# Pmaster-A9112-remote_1.net
KiCad netlist of a schematic drawn in Altium Designer
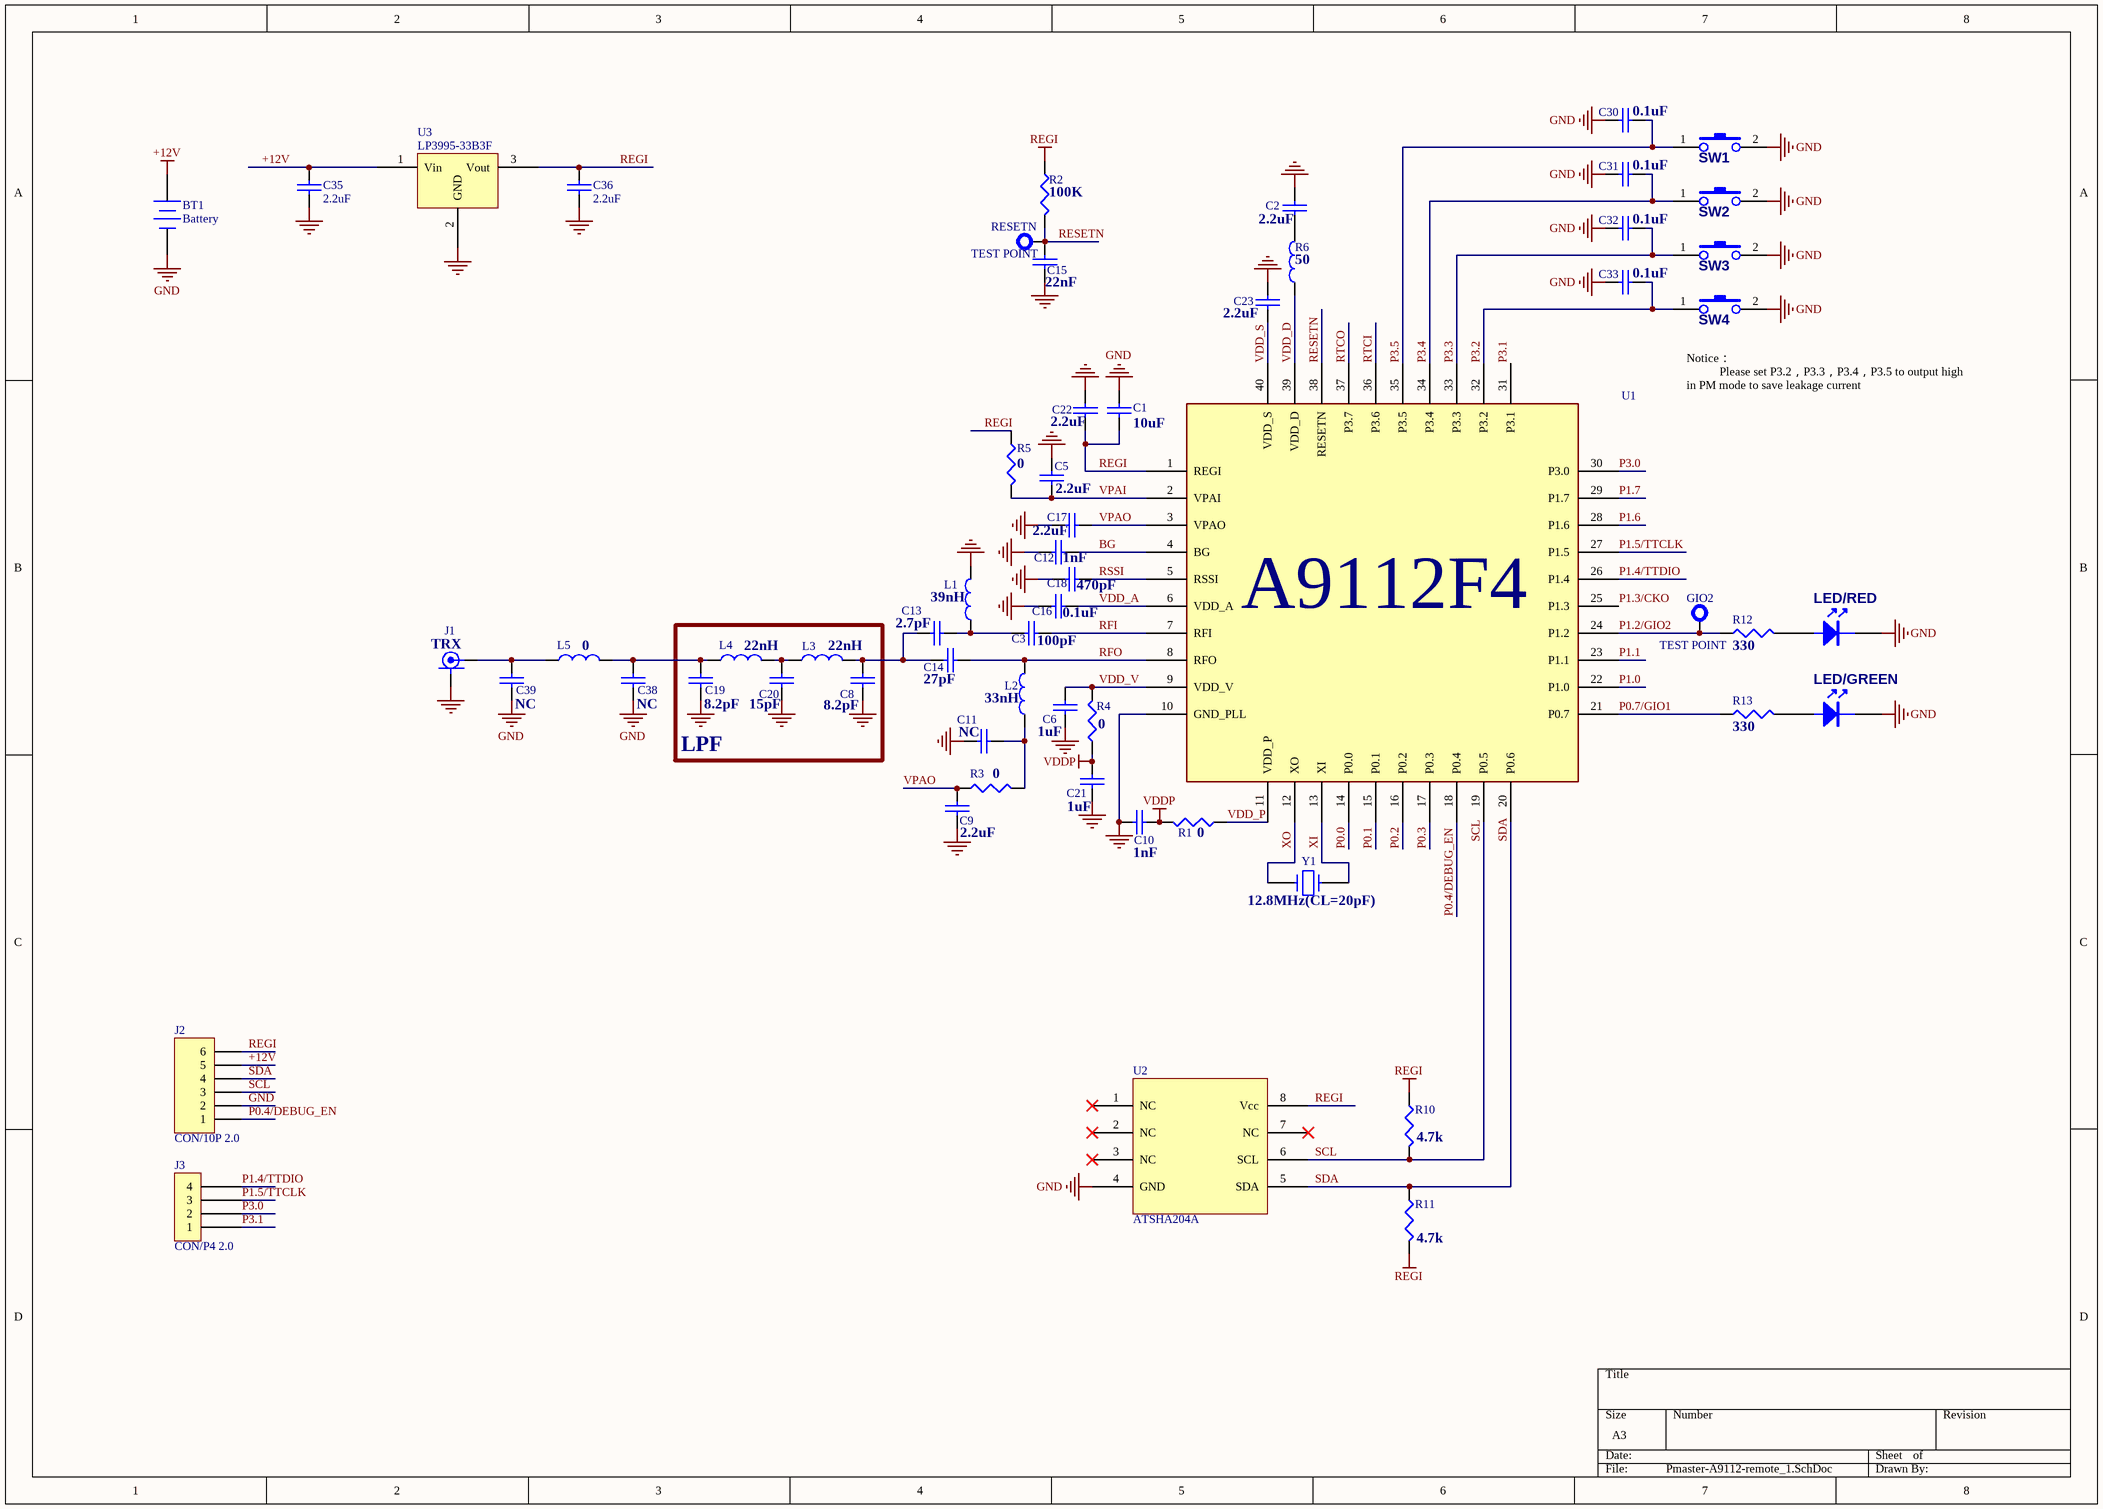
[diagram p0: Pmaster-A9112-remote_1.SchDoc]

(export (version "E")
  (design (tool "Eeschema 10.0.6"))
  (components
    (comp (ref "BT1")
      (value "Battery")
      (footprint "BAT-2")
      (description "Multicell Battery")
      (fields (field (name "PUBLISHER") "Altium Limited"))
      (libsource (lib "Miscellaneous Devices") (part "Battery"))
    )
    (comp (ref "C1") (value "10uF") (footprint "1206") (libsource (lib "*") (part "CAP")))
    (comp (ref "C2") (value "2.2uF") (footprint "0603") (libsource (lib "*") (part "CAP")))
    (comp (ref "C3") (value "100pF") (footprint "0402") (libsource (lib "*") (part "CAP")))
    (comp (ref "C5") (value "2.2uF") (footprint "0603") (libsource (lib "*") (part "CAP")))
    (comp (ref "C6") (value "1uF") (footprint "0603") (libsource (lib "*") (part "CAP")))
    (comp (ref "C8") (value "8.2pF") (footprint "0402") (libsource (lib "*") (part "CAP")))
    (comp (ref "C9")
      (value "2.2uF")
      (footprint "0603")
      (description "Chip C")
      (libsource (lib "*") (part "C/0603"))
    )
    (comp (ref "C10") (value "1nF") (footprint "0402") (libsource (lib "*") (part "CAP")))
    (comp (ref "C11")
      (value "NC")
      (footprint "0402")
      (description "Chip C")
      (libsource (lib "*") (part "C/0603"))
    )
    (comp (ref "C12") (value "1nF") (footprint "0402") (libsource (lib "*") (part "CAP")))
    (comp (ref "C13") (value "2.7pF") (footprint "0402") (libsource (lib "*") (part "CAP")))
    (comp (ref "C14") (value "27pF") (footprint "0402") (libsource (lib "*") (part "CAP")))
    (comp (ref "C15")
      (value "22nF")
      (footprint "0402")
      (description "Chip C")
      (libsource (lib "*") (part "C/1206"))
    )
    (comp (ref "C16") (value "0.1uF") (footprint "0603") (libsource (lib "*") (part "CAP")))
    (comp (ref "C17")
      (value "2.2uF")
      (footprint "0603")
      (description "Chip C")
      (libsource (lib "*") (part "C/0603"))
    )
    (comp (ref "C18") (value "470pF") (footprint "0402") (libsource (lib "*") (part "CAP")))
    (comp (ref "C19")
      (value "8.2pF")
      (footprint "0402")
      (description "Chip C")
      (libsource (lib "*") (part "C/0603"))
    )
    (comp (ref "C20")
      (value "15pF")
      (footprint "0402")
      (description "Chip C")
      (libsource (lib "*") (part "C/0603"))
    )
    (comp (ref "C21") (value "1uF") (footprint "0402") (libsource (lib "*") (part "CAP")))
    (comp (ref "C22") (value "2.2uF") (footprint "0603") (libsource (lib "*") (part "CAP")))
    (comp (ref "C23") (value "2.2uF") (footprint "0603") (libsource (lib "*") (part "CAP")))
    (comp (ref "C30") (value "0.1uF") (footprint "0603") (libsource (lib "*") (part "CAP")))
    (comp (ref "C31") (value "0.1uF") (footprint "0603") (libsource (lib "*") (part "CAP")))
    (comp (ref "C32") (value "0.1uF") (footprint "0603") (libsource (lib "*") (part "CAP")))
    (comp (ref "C33") (value "0.1uF") (footprint "0603") (libsource (lib "*") (part "CAP")))
    (comp (ref "C35") (value "2.2uF") (footprint "0603") (libsource (lib "") (part "CAP_1")))
    (comp (ref "C36")
      (value "2.2uF")
      (footprint "0603")
      (description "Chip C")
      (libsource (lib "*") (part "C/0603"))
    )
    (comp (ref "C38")
      (value "NC")
      (footprint "0402")
      (description "Chip C")
      (libsource (lib "*") (part "C/0603"))
    )
    (comp (ref "C39")
      (value "NC")
      (footprint "0402")
      (description "Chip C")
      (libsource (lib "*") (part "C/0603"))
    )
    (comp (ref "GIO2") (value "TEST POINT") (footprint "DIPOLE") (libsource (lib "my-amiccom") (part "TP")))
    (comp (ref "J1") (value "TRX") (footprint "SMA CONNECTOR") (libsource (lib "*") (part "SMA CONNECTOR")))
    (comp (ref "J2")
      (value "CON/10P 2.0")
      (footprint "HDR10_2.0")
      (description "Hole 36mil")
      (libsource (lib "my-amiccom") (part "CON/6P 2.0"))
    )
    (comp (ref "J3") (value "CON/P4 2.0") (libsource (lib "my-amiccom") (part "CON/P4 2.54")))
    (comp (ref "L1")
      (value "39nH")
      (footprint "0402")
      (description "Chip L")
      (libsource (lib "*") (part "L/0402"))
    )
    (comp (ref "L2")
      (value "33nH")
      (footprint "0402")
      (description "Chip L")
      (libsource (lib "*") (part "L/0402"))
    )
    (comp (ref "L3") (value "22nH") (footprint "0402") (libsource (lib "*") (part "L/0603")))
    (comp (ref "L4") (value "22nH") (footprint "0402") (libsource (lib "*") (part "L/0603")))
    (comp (ref "L5") (value "0") (footprint "0402") (libsource (lib "*") (part "L/0603")))
    (comp (ref "LED/GREEN")
      (value "LED/GREEN")
      (footprint "0603")
      (libsource (lib "my-amiccom") (part "LED"))
    )
    (comp (ref "LED/RED") (value "LED/RED") (footprint "0603") (libsource (lib "my-amiccom") (part "LED")))
    (comp (ref "R1") (value "0") (footprint "0402") (libsource (lib "*") (part "RES1")))
    (comp (ref "R2")
      (value "100K")
      (footprint "0402")
      (description "Chip R")
      (libsource (lib "*") (part "R/0402"))
    )
    (comp (ref "R3")
      (value "0")
      (footprint "0402")
      (description "Chip  R")
      (libsource (lib "*") (part "R/0603"))
    )
    (comp (ref "R4")
      (value "0")
      (footprint "0402")
      (description "Chip  R")
      (libsource (lib "*") (part "R/0603"))
    )
    (comp (ref "R5") (value "0") (footprint "0402") (libsource (lib "*") (part "RES1")))
    (comp (ref "R6") (value "50") (footprint "0402") (libsource (lib "") (part "L/0603_1")))
    (comp (ref "R10") (value "4.7k") (footprint "0402") (libsource (lib "*") (part "RES1")))
    (comp (ref "R11") (value "4.7k") (footprint "0402") (libsource (lib "*") (part "RES1")))
    (comp (ref "R12") (value "330") (footprint "0402") (libsource (lib "*") (part "RES1")))
    (comp (ref "R13") (value "330") (footprint "0402") (libsource (lib "*") (part "RES1")))
    (comp (ref "RESETN") (value "TEST POINT") (footprint "DIPOLE") (libsource (lib "my-amiccom") (part "TP")))
    (comp (ref "SW1")
      (value "SW-P~{B}2P")
      (footprint "SW2P")
      (libsource (lib "my-amiccom") (part "SW-PB{backslash}2P"))
    )
    (comp (ref "SW2")
      (value "SW-P~{B}2P")
      (footprint "SW2P")
      (libsource (lib "my-amiccom") (part "SW-PB{backslash}2P"))
    )
    (comp (ref "SW3")
      (value "SW-P~{B}2P")
      (footprint "SW2P")
      (libsource (lib "my-amiccom") (part "SW-PB{backslash}2P"))
    )
    (comp (ref "SW4")
      (value "SW-P~{B}2P")
      (footprint "SW2P")
      (libsource (lib "my-amiccom") (part "SW-PB{backslash}2P"))
    )
    (comp (ref "U1")
      (value "A9112F4")
      (footprint "QFN 5*5 40L")
      (libsource (lib "AMICCOM-S") (part "A9112F4"))
    )
    (comp (ref "U2") (value "ATSHA204A") (libsource (lib "my-amiccom") (part "ATSHA204A")))
    (comp (ref "U3")
      (value "LP3995-33B3F")
      (footprint "SOT-223")
      (description "GMT 3.3V REGULTOR")
      (libsource (lib "*") (part "REG{backslash}G903{backslash}3.3V{backslash}SOT-223"))
    )
    (comp (ref "Y1")
      (value "12.8MHz(CL=20pF)")
      (footprint "XTAL1")
      (description "Crystal")
      (libsource (lib "*") (part "CRYSTAL"))
    )
  )
  (nets
    (net (code "1") (name "+12V") (class "Default")
      (node (ref "BT1") (pin "1") (pinfunction "+_1") (pintype "passive"))
      (node (ref "C35") (pin "2") (pinfunction "2_2") (pintype "passive"))
      (node (ref "J2") (pin "5") (pinfunction "5_5") (pintype "passive"))
      (node (ref "U3") (pin "1") (pinfunction "Vin_1") (pintype "passive"))
    )
    (net (code "2") (name "/BG") (class "Default")
      (node (ref "C12") (pin "1") (pinfunction "1_1") (pintype "passive"))
      (node (ref "U1") (pin "4") (pinfunction "BG_4") (pintype "passive"))
    )
    (net (code "3") (name "/P0.0") (class "Default")
      (node (ref "U1") (pin "14") (pinfunction "P0.0_14") (pintype "passive"))
    )
    (net (code "4") (name "/P0.1") (class "Default")
      (node (ref "U1") (pin "15") (pinfunction "P0.1_15") (pintype "passive"))
    )
    (net (code "5") (name "/P0.2") (class "Default")
      (node (ref "U1") (pin "16") (pinfunction "P0.2_16") (pintype "passive"))
    )
    (net (code "6") (name "/P0.3") (class "Default")
      (node (ref "U1") (pin "17") (pinfunction "P0.3_17") (pintype "passive"))
    )
    (net (code "7") (name "/P0.4{slash}DEBUG_EN") (class "Default")
      (node (ref "J2") (pin "1") (pinfunction "1_1") (pintype "passive"))
      (node (ref "U1") (pin "18") (pinfunction "P0.4_18") (pintype "passive"))
    )
    (net (code "8") (name "/P0.7{slash}GIO1") (class "Default")
      (node (ref "R13") (pin "1") (pinfunction "1_1") (pintype "passive"))
      (node (ref "U1") (pin "21") (pinfunction "P0.7_21") (pintype "passive"))
    )
    (net (code "9") (name "/P1.0") (class "Default")
      (node (ref "U1") (pin "22") (pinfunction "P1.0_22") (pintype "passive"))
    )
    (net (code "10") (name "/P1.1") (class "Default")
      (node (ref "U1") (pin "23") (pinfunction "P1.1_23") (pintype "passive"))
    )
    (net (code "11") (name "/P1.2{slash}GIO2") (class "Default")
      (node (ref "GIO2") (pin "1") (pinfunction "1_1") (pintype "passive"))
      (node (ref "R12") (pin "1") (pinfunction "1_1") (pintype "passive"))
      (node (ref "U1") (pin "24") (pinfunction "P1.2_24") (pintype "passive"))
    )
    (net (code "12") (name "/P1.3{slash}CKO") (class "Default")
      (node (ref "U1") (pin "25") (pinfunction "P1.3_25") (pintype "passive"))
    )
    (net (code "13") (name "/P1.4{slash}TTDIO") (class "Default")
      (node (ref "J3") (pin "4") (pinfunction "4_4") (pintype "power_in"))
      (node (ref "U1") (pin "26") (pinfunction "P1.4_26") (pintype "passive"))
    )
    (net (code "14") (name "/P1.5{slash}TTCLK") (class "Default")
      (node (ref "J3") (pin "3") (pinfunction "3_3") (pintype "power_in"))
      (node (ref "U1") (pin "27") (pinfunction "P1.5_27") (pintype "passive"))
    )
    (net (code "15") (name "/P1.6") (class "Default")
      (node (ref "U1") (pin "28") (pinfunction "P1.6_28") (pintype "passive"))
    )
    (net (code "16") (name "/P1.7") (class "Default")
      (node (ref "U1") (pin "29") (pinfunction "P1.7_29") (pintype "passive"))
    )
    (net (code "17") (name "/P3.0") (class "Default")
      (node (ref "J3") (pin "2") (pinfunction "2_2") (pintype "power_in"))
      (node (ref "U1") (pin "30") (pinfunction "P3.0_30") (pintype "passive"))
    )
    (net (code "18") (name "/P3.1") (class "Default")
      (node (ref "J3") (pin "1") (pinfunction "1_1") (pintype "power_in"))
      (node (ref "U1") (pin "31") (pinfunction "P3.1_31") (pintype "passive"))
    )
    (net (code "19") (name "/P3.2") (class "Default")
      (node (ref "C33") (pin "2") (pinfunction "2_2") (pintype "passive"))
      (node (ref "SW4") (pin "1") (pinfunction "1_1") (pintype "passive"))
      (node (ref "U1") (pin "32") (pinfunction "P3.2_32") (pintype "passive"))
    )
    (net (code "20") (name "/P3.3") (class "Default")
      (node (ref "C32") (pin "2") (pinfunction "2_2") (pintype "passive"))
      (node (ref "SW3") (pin "1") (pinfunction "1_1") (pintype "passive"))
      (node (ref "U1") (pin "33") (pinfunction "P3.3_33") (pintype "passive"))
    )
    (net (code "21") (name "/P3.4") (class "Default")
      (node (ref "C31") (pin "2") (pinfunction "2_2") (pintype "passive"))
      (node (ref "SW2") (pin "1") (pinfunction "1_1") (pintype "passive"))
      (node (ref "U1") (pin "34") (pinfunction "P3.4_34") (pintype "passive"))
    )
    (net (code "22") (name "/P3.5") (class "Default")
      (node (ref "C30") (pin "2") (pinfunction "2_2") (pintype "passive"))
      (node (ref "SW1") (pin "1") (pinfunction "1_1") (pintype "passive"))
      (node (ref "U1") (pin "35") (pinfunction "P3.5_35") (pintype "passive"))
    )
    (net (code "23") (name "/RESETN") (class "Default")
      (node (ref "C15") (pin "1") (pinfunction "1_1") (pintype "passive"))
      (node (ref "R2") (pin "2") (pinfunction "2_2") (pintype "passive"))
      (node (ref "RESETN") (pin "1") (pinfunction "1_1") (pintype "passive"))
      (node (ref "U1") (pin "38") (pinfunction "RESETN_38") (pintype "passive"))
    )
    (net (code "24") (name "/RFI") (class "Default")
      (node (ref "C3") (pin "1") (pinfunction "1_1") (pintype "passive"))
      (node (ref "U1") (pin "7") (pinfunction "RFI_7") (pintype "passive"))
    )
    (net (code "25") (name "/RFO") (class "Default")
      (node (ref "C14") (pin "1") (pinfunction "1_1") (pintype "passive"))
      (node (ref "L2") (pin "2") (pinfunction "2_2") (pintype "passive"))
      (node (ref "U1") (pin "8") (pinfunction "RFO_8") (pintype "passive"))
    )
    (net (code "26") (name "/RSSI") (class "Default")
      (node (ref "C18") (pin "2") (pinfunction "2_2") (pintype "passive"))
      (node (ref "U1") (pin "5") (pinfunction "RSSI_5") (pintype "passive"))
    )
    (net (code "27") (name "/RTCI") (class "Default")
      (node (ref "U1") (pin "36") (pinfunction "P3.6_36") (pintype "passive"))
    )
    (net (code "28") (name "/RTCO") (class "Default")
      (node (ref "U1") (pin "37") (pinfunction "P3.7_37") (pintype "passive"))
    )
    (net (code "29") (name "/SCL") (class "Default")
      (node (ref "J2") (pin "3") (pinfunction "3_3") (pintype "passive"))
      (node (ref "R10") (pin "2") (pinfunction "2_2") (pintype "passive"))
      (node (ref "U1") (pin "19") (pinfunction "P0.5_19") (pintype "passive"))
      (node (ref "U2") (pin "6") (pinfunction "SCL_6") (pintype "passive"))
    )
    (net (code "30") (name "/SDA") (class "Default")
      (node (ref "J2") (pin "4") (pinfunction "4_4") (pintype "passive"))
      (node (ref "R11") (pin "1") (pinfunction "1_1") (pintype "passive"))
      (node (ref "U1") (pin "20") (pinfunction "P0.6_20") (pintype "passive"))
      (node (ref "U2") (pin "5") (pinfunction "SDA_5") (pintype "passive"))
    )
    (net (code "31") (name "/VDD_A") (class "Default")
      (node (ref "C16") (pin "2") (pinfunction "2_2") (pintype "passive"))
      (node (ref "U1") (pin "6") (pinfunction "VDD_A_6") (pintype "passive"))
    )
    (net (code "32") (name "/VDD_D") (class "Default")
      (node (ref "R6") (pin "1") (pinfunction "1_1") (pintype "passive"))
      (node (ref "U1") (pin "39") (pinfunction "VDD_D_39") (pintype "passive"))
    )
    (net (code "33") (name "/VDD_P") (class "Default")
      (node (ref "R1") (pin "1") (pinfunction "1_1") (pintype "passive"))
      (node (ref "U1") (pin "11") (pinfunction "VDD_P_11") (pintype "passive"))
    )
    (net (code "35") (name "/VDD_S") (class "Default")
      (node (ref "C23") (pin "2") (pinfunction "2_2") (pintype "passive"))
      (node (ref "U1") (pin "40") (pinfunction "VDD_S_40") (pintype "passive"))
    )
    (net (code "36") (name "/VDD_V") (class "Default")
      (node (ref "C6") (pin "1") (pinfunction "1_1") (pintype "passive"))
      (node (ref "R4") (pin "2") (pinfunction "2_2") (pintype "passive"))
      (node (ref "U1") (pin "9") (pinfunction "VDD_V_9") (pintype "passive"))
    )
    (net (code "37") (name "/VPAI") (class "Default")
      (node (ref "C5") (pin "1") (pinfunction "1_1") (pintype "passive"))
      (node (ref "R5") (pin "2") (pinfunction "2_2") (pintype "passive"))
      (node (ref "U1") (pin "2") (pinfunction "VPAI_2") (pintype "passive"))
    )
    (net (code "38") (name "/VPAO") (class "Default")
      (node (ref "C17") (pin "1") (pinfunction "1_1") (pintype "passive"))
      (node (ref "C9") (pin "1") (pinfunction "1_1") (pintype "passive"))
      (node (ref "R3") (pin "1") (pinfunction "1_1") (pintype "passive"))
      (node (ref "U1") (pin "3") (pinfunction "VPAO_3") (pintype "passive"))
    )
    (net (code "39") (name "/XI") (class "Default")
      (node (ref "U1") (pin "13") (pinfunction "XI_13") (pintype "passive"))
      (node (ref "Y1") (pin "1") (pinfunction "1_1") (pintype "passive"))
    )
    (net (code "40") (name "/XO") (class "Default")
      (node (ref "U1") (pin "12") (pinfunction "XO_12") (pintype "passive"))
      (node (ref "Y1") (pin "2") (pinfunction "2_2") (pintype "passive"))
    )
    (net (code "41") (name "GND") (class "Default")
      (node (ref "BT1") (pin "2") (pinfunction "-_2") (pintype "passive"))
      (node (ref "C1") (pin "2") (pinfunction "2_2") (pintype "passive"))
      (node (ref "C10") (pin "1") (pinfunction "1_1") (pintype "passive"))
      (node (ref "C11") (pin "1") (pinfunction "1_1") (pintype "passive"))
      (node (ref "C12") (pin "2") (pinfunction "2_2") (pintype "passive"))
      (node (ref "C15") (pin "2") (pinfunction "2_2") (pintype "passive"))
      (node (ref "C16") (pin "1") (pinfunction "1_1") (pintype "passive"))
      (node (ref "C17") (pin "2") (pinfunction "2_2") (pintype "passive"))
      (node (ref "C18") (pin "1") (pinfunction "1_1") (pintype "passive"))
      (node (ref "C19") (pin "2") (pinfunction "2_2") (pintype "passive"))
      (node (ref "C2") (pin "1") (pinfunction "1_1") (pintype "passive"))
      (node (ref "C20") (pin "2") (pinfunction "2_2") (pintype "passive"))
      (node (ref "C21") (pin "1") (pinfunction "1_1") (pintype "passive"))
      (node (ref "C22") (pin "1") (pinfunction "1_1") (pintype "passive"))
      (node (ref "C23") (pin "1") (pinfunction "1_1") (pintype "passive"))
      (node (ref "C30") (pin "1") (pinfunction "1_1") (pintype "passive"))
      (node (ref "C31") (pin "1") (pinfunction "1_1") (pintype "passive"))
      (node (ref "C32") (pin "1") (pinfunction "1_1") (pintype "passive"))
      (node (ref "C33") (pin "1") (pinfunction "1_1") (pintype "passive"))
      (node (ref "C35") (pin "1") (pinfunction "1_1") (pintype "passive"))
      (node (ref "C36") (pin "2") (pinfunction "2_2") (pintype "passive"))
      (node (ref "C38") (pin "2") (pinfunction "2_2") (pintype "passive"))
      (node (ref "C39") (pin "2") (pinfunction "2_2") (pintype "passive"))
      (node (ref "C5") (pin "2") (pinfunction "2_2") (pintype "passive"))
      (node (ref "C8") (pin "1") (pinfunction "1_1") (pintype "passive"))
      (node (ref "C9") (pin "2") (pinfunction "2_2") (pintype "passive"))
      (node (ref "J1") (pin "0") (pinfunction "SHIELD_0") (pintype "passive"))
      (node (ref "J2") (pin "2") (pinfunction "2_2") (pintype "passive"))
      (node (ref "L1") (pin "2") (pinfunction "2_2") (pintype "passive"))
      (node (ref "LED/GREEN") (pin "2") (pinfunction "K_2") (pintype "passive"))
      (node (ref "LED/RED") (pin "2") (pinfunction "K_2") (pintype "passive"))
      (node (ref "SW1") (pin "2") (pinfunction "2_2") (pintype "passive"))
      (node (ref "SW2") (pin "2") (pinfunction "2_2") (pintype "passive"))
      (node (ref "SW3") (pin "2") (pinfunction "2_2") (pintype "passive"))
      (node (ref "SW4") (pin "2") (pinfunction "2_2") (pintype "passive"))
      (node (ref "U1") (pin "10") (pinfunction "GND_PLL_10") (pintype "passive"))
      (node (ref "U2") (pin "4") (pinfunction "GND_4") (pintype "passive"))
      (node (ref "U3") (pin "2") (pinfunction "GND_2") (pintype "passive"))
    )
    (net (code "42") (name "Net-(C2-Pad2)") (class "Default")
      (node (ref "C2") (pin "2") (pinfunction "2_2") (pintype "passive"))
      (node (ref "R6") (pin "2") (pinfunction "2_2") (pintype "passive"))
    )
    (net (code "43") (name "Net-(C11-Pad2)") (class "Default")
      (node (ref "C11") (pin "2") (pinfunction "2_2") (pintype "passive"))
      (node (ref "L2") (pin "1") (pinfunction "1_1") (pintype "passive"))
      (node (ref "R3") (pin "2") (pinfunction "2_2") (pintype "passive"))
    )
    (net (code "44") (name "Net-(C13-Pad1)") (class "Default")
      (node (ref "C13") (pin "1") (pinfunction "1_1") (pintype "passive"))
      (node (ref "C3") (pin "2") (pinfunction "2_2") (pintype "passive"))
      (node (ref "L1") (pin "1") (pinfunction "1_1") (pintype "passive"))
    )
    (net (code "45") (name "Net-(C13-Pad2)") (class "Default")
      (node (ref "C13") (pin "2") (pinfunction "2_2") (pintype "passive"))
      (node (ref "C14") (pin "2") (pinfunction "2_2") (pintype "passive"))
      (node (ref "C8") (pin "2") (pinfunction "2_2") (pintype "passive"))
      (node (ref "L3") (pin "2") (pinfunction "2_2") (pintype "passive"))
    )
    (net (code "46") (name "Net-(C19-Pad1)") (class "Default")
      (node (ref "C19") (pin "1") (pinfunction "1_1") (pintype "passive"))
      (node (ref "C38") (pin "1") (pinfunction "1_1") (pintype "passive"))
      (node (ref "L4") (pin "1") (pinfunction "1_1") (pintype "passive"))
      (node (ref "L5") (pin "2") (pinfunction "2_2") (pintype "passive"))
    )
    (net (code "47") (name "Net-(C20-Pad1)") (class "Default")
      (node (ref "C20") (pin "1") (pinfunction "1_1") (pintype "passive"))
      (node (ref "L3") (pin "1") (pinfunction "1_1") (pintype "passive"))
      (node (ref "L4") (pin "2") (pinfunction "2_2") (pintype "passive"))
    )
    (net (code "48") (name "Net-(J1-CENTER_1)") (class "Default")
      (node (ref "C39") (pin "1") (pinfunction "1_1") (pintype "passive"))
      (node (ref "J1") (pin "1") (pinfunction "CENTER_1_1") (pintype "passive"))
      (node (ref "L5") (pin "1") (pinfunction "1_1") (pintype "passive"))
    )
    (net (code "49") (name "Net-(LED/GREEN-A)") (class "Default")
      (node (ref "LED/GREEN") (pin "1") (pinfunction "A_1") (pintype "passive"))
      (node (ref "R13") (pin "2") (pinfunction "2_2") (pintype "passive"))
    )
    (net (code "50") (name "Net-(LED/RED-A)") (class "Default")
      (node (ref "LED/RED") (pin "1") (pinfunction "A_1") (pintype "passive"))
      (node (ref "R12") (pin "2") (pinfunction "2_2") (pintype "passive"))
    )
    (net (code "51") (name "REGI") (class "Default")
      (node (ref "C1") (pin "1") (pinfunction "1_1") (pintype "passive"))
      (node (ref "C22") (pin "2") (pinfunction "2_2") (pintype "passive"))
      (node (ref "C36") (pin "1") (pinfunction "1_1") (pintype "passive"))
      (node (ref "J2") (pin "6") (pinfunction "6_6") (pintype "passive"))
      (node (ref "R10") (pin "1") (pinfunction "1_1") (pintype "passive"))
      (node (ref "R11") (pin "2") (pinfunction "2_2") (pintype "passive"))
      (node (ref "R2") (pin "1") (pinfunction "1_1") (pintype "passive"))
      (node (ref "R5") (pin "1") (pinfunction "1_1") (pintype "passive"))
      (node (ref "U1") (pin "1") (pinfunction "REGI_1") (pintype "passive"))
      (node (ref "U2") (pin "8") (pinfunction "Vcc_8") (pintype "passive"))
      (node (ref "U3") (pin "3") (pinfunction "Vout_3") (pintype "passive"))
    )
    (net (code "52") (name "VCO_GND") (class "Default")
      (node (ref "C6") (pin "2") (pinfunction "2_2") (pintype "passive"))
    )
    (net (code "53") (name "VDDP") (class "Default")
      (node (ref "C10") (pin "2") (pinfunction "2_2") (pintype "passive"))
      (node (ref "C21") (pin "2") (pinfunction "2_2") (pintype "passive"))
      (node (ref "R1") (pin "2") (pinfunction "2_2") (pintype "passive"))
      (node (ref "R4") (pin "1") (pinfunction "1_1") (pintype "passive"))
    )
    (net (code "54") (name "unconnected-(U2-NC-Pad1)") (class "Default")
      (node (ref "U2") (pin "1") (pinfunction "NC_1") (pintype "passive+no_connect"))
    )
    (net (code "55") (name "unconnected-(U2-NC-Pad2)") (class "Default")
      (node (ref "U2") (pin "2") (pinfunction "NC_2") (pintype "passive+no_connect"))
    )
    (net (code "56") (name "unconnected-(U2-NC-Pad3)") (class "Default")
      (node (ref "U2") (pin "3") (pinfunction "NC_3") (pintype "passive+no_connect"))
    )
    (net (code "57") (name "unconnected-(U2-NC-Pad7)") (class "Default")
      (node (ref "U2") (pin "7") (pinfunction "NC_7") (pintype "passive+no_connect"))
    )
  )
)
